# Gamepad.net
KiCad netlist of a schematic drawn in EAGLE
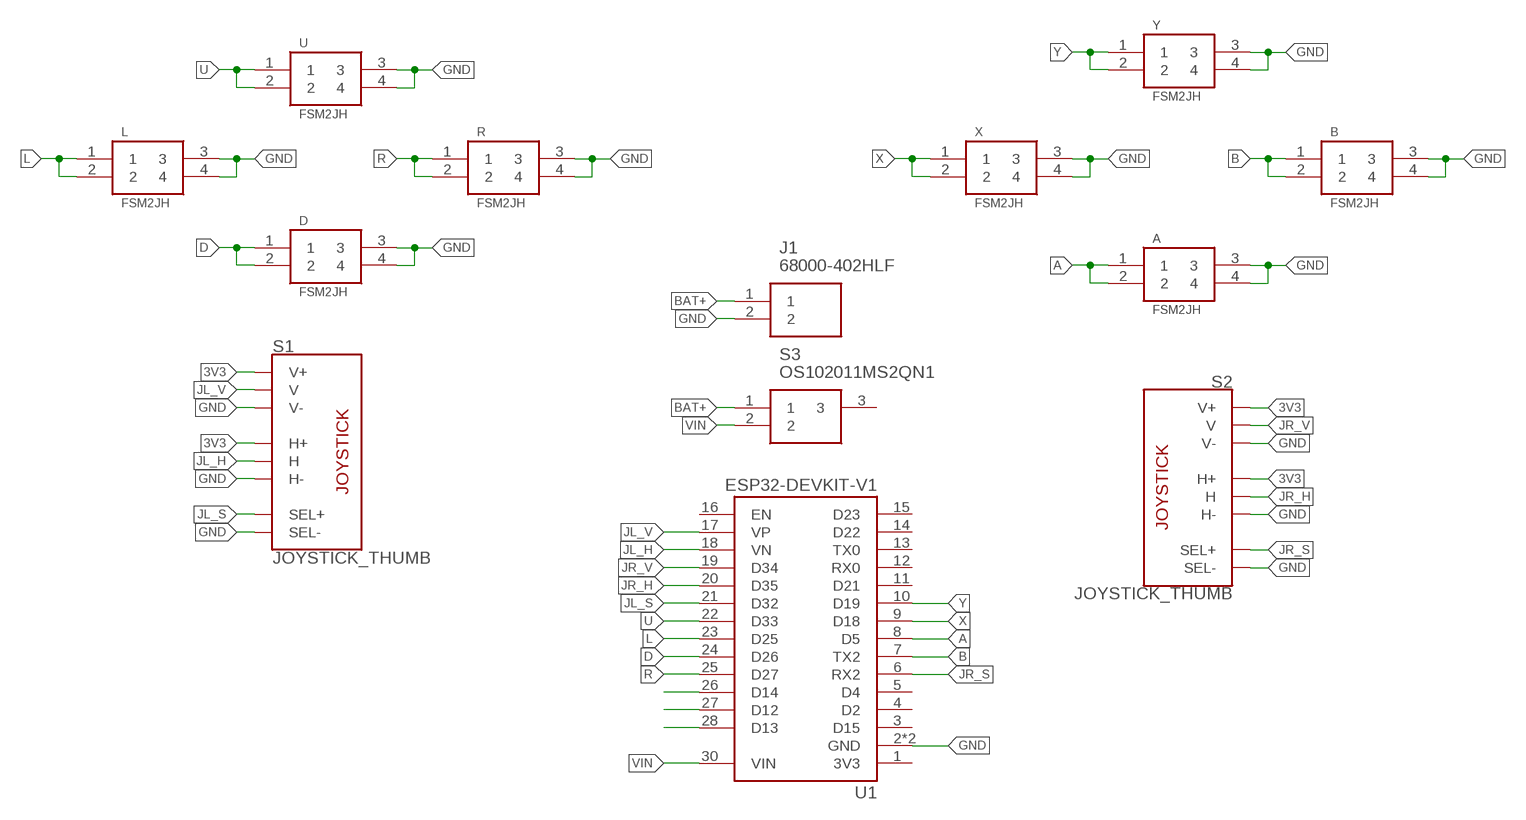
[diagram p0: schematic, sheet 1]

(export (version "E")
  (design (tool "Eeschema 10.0.6"))
  (components
    (comp (ref "A")
      (value "FSM2JH")
      (footprint "eagle-import:FSM2JH")
      (libsource (lib "eagle-import") (part "FSM2JH"))
    )
    (comp (ref "B")
      (value "FSM2JH")
      (footprint "eagle-import:FSM2JH")
      (libsource (lib "eagle-import") (part "FSM2JH"))
    )
    (comp (ref "D")
      (value "FSM2JH")
      (footprint "eagle-import:FSM2JH")
      (libsource (lib "eagle-import") (part "FSM2JH"))
    )
    (comp (ref "J1")
      (value "68000-402HLF")
      (footprint "eagle-import:68000-402HLF")
      (fields (field (name "MOUSER_PART_NUMBER") "649-68000-402HLF"))
      (libsource (lib "eagle-import") (part "68000-402HLF"))
    )
    (comp (ref "L")
      (value "FSM2JH")
      (footprint "eagle-import:FSM2JH")
      (libsource (lib "eagle-import") (part "FSM2JH"))
    )
    (comp (ref "R")
      (value "FSM2JH")
      (footprint "eagle-import:FSM2JH")
      (libsource (lib "eagle-import") (part "FSM2JH"))
    )
    (comp (ref "S1")
      (value "JOYSTICK_THUMB")
      (footprint "eagle-import:JOYSTICK")
      (libsource (lib "eagle-import") (part "JOYSTICK_THUMB"))
    )
    (comp (ref "S2")
      (value "JOYSTICK_THUMB")
      (footprint "eagle-import:JOYSTICK")
      (libsource (lib "eagle-import") (part "JOYSTICK_THUMB"))
    )
    (comp (ref "S3")
      (value "OS102011MS2QN1")
      (footprint "eagle-import:OS102011MA1QN1")
      (fields (field (name "RS_PART_NUMBER") "7874864"))
      (libsource (lib "eagle-import") (part "OS102011MS2QN1"))
    )
    (comp (ref "U")
      (value "FSM2JH")
      (footprint "eagle-import:FSM2JH")
      (libsource (lib "eagle-import") (part "FSM2JH"))
    )
    (comp (ref "U1")
      (value "ESP32-DEVKIT-V1")
      (footprint "eagle-import:MODULE_ESP32_DEVKIT_V1")
      (fields (field (name "MF") "Do it"))
      (libsource (lib "eagle-import") (part "ESP32-DEVKIT-V1"))
    )
    (comp (ref "X")
      (value "FSM2JH")
      (footprint "eagle-import:FSM2JH")
      (libsource (lib "eagle-import") (part "FSM2JH"))
    )
    (comp (ref "Y")
      (value "FSM2JH")
      (footprint "eagle-import:FSM2JH")
      (libsource (lib "eagle-import") (part "FSM2JH"))
    )
  )
  (nets
    (net (code "1") (name "3V3") (class "Default")
      (node (ref "S1") (pin "H1") (pinfunction "H+_H1") (pintype "bidirectional"))
      (node (ref "S1") (pin "V1") (pinfunction "V+_V1") (pintype "bidirectional"))
      (node (ref "S2") (pin "H1") (pinfunction "H+_H1") (pintype "bidirectional"))
      (node (ref "S2") (pin "V1") (pinfunction "V+_V1") (pintype "bidirectional"))
    )
    (net (code "2") (name "A") (class "Default")
      (node (ref "A") (pin "1") (pinfunction "1_1") (pintype "bidirectional"))
      (node (ref "A") (pin "2") (pinfunction "2_2") (pintype "bidirectional"))
      (node (ref "U1") (pin "8") (pinfunction "D5_8") (pintype "bidirectional"))
    )
    (net (code "3") (name "B") (class "Default")
      (node (ref "B") (pin "1") (pinfunction "1_1") (pintype "bidirectional"))
      (node (ref "B") (pin "2") (pinfunction "2_2") (pintype "bidirectional"))
      (node (ref "U1") (pin "7") (pinfunction "TX2_7") (pintype "output"))
    )
    (net (code "4") (name "BAT+") (class "Default")
      (node (ref "J1") (pin "1") (pinfunction "1_1") (pintype "bidirectional"))
      (node (ref "S3") (pin "1") (pinfunction "1_1") (pintype "bidirectional"))
    )
    (net (code "5") (name "D") (class "Default")
      (node (ref "D") (pin "1") (pinfunction "1_1") (pintype "bidirectional"))
      (node (ref "D") (pin "2") (pinfunction "2_2") (pintype "bidirectional"))
      (node (ref "U1") (pin "24") (pinfunction "D26_24") (pintype "bidirectional"))
    )
    (net (code "6") (name "GND") (class "Default")
      (node (ref "A") (pin "3") (pinfunction "3_3") (pintype "bidirectional"))
      (node (ref "A") (pin "4") (pinfunction "4_4") (pintype "bidirectional"))
      (node (ref "B") (pin "3") (pinfunction "3_3") (pintype "bidirectional"))
      (node (ref "B") (pin "4") (pinfunction "4_4") (pintype "bidirectional"))
      (node (ref "D") (pin "3") (pinfunction "3_3") (pintype "bidirectional"))
      (node (ref "D") (pin "4") (pinfunction "4_4") (pintype "bidirectional"))
      (node (ref "J1") (pin "2") (pinfunction "2_2") (pintype "bidirectional"))
      (node (ref "L") (pin "3") (pinfunction "3_3") (pintype "bidirectional"))
      (node (ref "L") (pin "4") (pinfunction "4_4") (pintype "bidirectional"))
      (node (ref "R") (pin "3") (pinfunction "3_3") (pintype "bidirectional"))
      (node (ref "R") (pin "4") (pinfunction "4_4") (pintype "bidirectional"))
      (node (ref "S1") (pin "B2A") (pinfunction "SEL-_B2A") (pintype "bidirectional"))
      (node (ref "S1") (pin "H3") (pinfunction "H-_H3") (pintype "bidirectional"))
      (node (ref "S1") (pin "V3") (pinfunction "V-_V3") (pintype "bidirectional"))
      (node (ref "S2") (pin "B2A") (pinfunction "SEL-_B2A") (pintype "bidirectional"))
      (node (ref "S2") (pin "H3") (pinfunction "H-_H3") (pintype "bidirectional"))
      (node (ref "S2") (pin "V3") (pinfunction "V-_V3") (pintype "bidirectional"))
      (node (ref "U") (pin "3") (pinfunction "3_3") (pintype "bidirectional"))
      (node (ref "U") (pin "4") (pinfunction "4_4") (pintype "bidirectional"))
      (node (ref "U1") (pin "2") (pinfunction "GND_2") (pintype "power_in"))
      (node (ref "U1") (pin "29") (pinfunction "GND_29") (pintype "power_in"))
      (node (ref "X") (pin "3") (pinfunction "3_3") (pintype "bidirectional"))
      (node (ref "X") (pin "4") (pinfunction "4_4") (pintype "bidirectional"))
      (node (ref "Y") (pin "3") (pinfunction "3_3") (pintype "bidirectional"))
      (node (ref "Y") (pin "4") (pinfunction "4_4") (pintype "bidirectional"))
    )
    (net (code "7") (name "JL_H") (class "Default")
      (node (ref "S1") (pin "H2") (pinfunction "H_H2") (pintype "bidirectional"))
      (node (ref "U1") (pin "18") (pinfunction "VN_18") (pintype "bidirectional"))
    )
    (net (code "8") (name "JL_S") (class "Default")
      (node (ref "S1") (pin "B1A") (pinfunction "SEL+_B1A") (pintype "bidirectional"))
      (node (ref "U1") (pin "21") (pinfunction "D32_21") (pintype "bidirectional"))
    )
    (net (code "9") (name "JL_V") (class "Default")
      (node (ref "S1") (pin "V2") (pinfunction "V_V2") (pintype "bidirectional"))
      (node (ref "U1") (pin "17") (pinfunction "VP_17") (pintype "bidirectional"))
    )
    (net (code "10") (name "JR_H") (class "Default")
      (node (ref "S2") (pin "H2") (pinfunction "H_H2") (pintype "bidirectional"))
      (node (ref "U1") (pin "20") (pinfunction "D35_20") (pintype "bidirectional"))
    )
    (net (code "11") (name "JR_S") (class "Default")
      (node (ref "S2") (pin "B1A") (pinfunction "SEL+_B1A") (pintype "bidirectional"))
      (node (ref "U1") (pin "6") (pinfunction "RX2_6") (pintype "input"))
    )
    (net (code "12") (name "JR_V") (class "Default")
      (node (ref "S2") (pin "V2") (pinfunction "V_V2") (pintype "bidirectional"))
      (node (ref "U1") (pin "19") (pinfunction "D34_19") (pintype "bidirectional"))
    )
    (net (code "13") (name "L") (class "Default")
      (node (ref "L") (pin "1") (pinfunction "1_1") (pintype "bidirectional"))
      (node (ref "L") (pin "2") (pinfunction "2_2") (pintype "bidirectional"))
      (node (ref "U1") (pin "23") (pinfunction "D25_23") (pintype "bidirectional"))
    )
    (net (code "14") (name "R") (class "Default")
      (node (ref "R") (pin "1") (pinfunction "1_1") (pintype "bidirectional"))
      (node (ref "R") (pin "2") (pinfunction "2_2") (pintype "bidirectional"))
      (node (ref "U1") (pin "25") (pinfunction "D27_25") (pintype "bidirectional"))
    )
    (net (code "15") (name "U") (class "Default")
      (node (ref "U") (pin "1") (pinfunction "1_1") (pintype "bidirectional"))
      (node (ref "U") (pin "2") (pinfunction "2_2") (pintype "bidirectional"))
      (node (ref "U1") (pin "22") (pinfunction "D33_22") (pintype "bidirectional"))
    )
    (net (code "16") (name "VIN") (class "Default")
      (node (ref "S3") (pin "2") (pinfunction "2_2") (pintype "bidirectional"))
      (node (ref "U1") (pin "30") (pinfunction "VIN_30") (pintype "input"))
    )
    (net (code "17") (name "X") (class "Default")
      (node (ref "U1") (pin "9") (pinfunction "D18_9") (pintype "bidirectional"))
      (node (ref "X") (pin "1") (pinfunction "1_1") (pintype "bidirectional"))
      (node (ref "X") (pin "2") (pinfunction "2_2") (pintype "bidirectional"))
    )
    (net (code "18") (name "Y") (class "Default")
      (node (ref "U1") (pin "10") (pinfunction "D19_10") (pintype "bidirectional"))
      (node (ref "Y") (pin "1") (pinfunction "1_1") (pintype "bidirectional"))
      (node (ref "Y") (pin "2") (pinfunction "2_2") (pintype "bidirectional"))
    )
    (net (code "19") (name "unconnected-(S3-Pad3)") (class "Default")
      (node (ref "S3") (pin "3") (pinfunction "3_3") (pintype "bidirectional"))
    )
    (net (code "20") (name "unconnected-(U1-3V3-Pad1)") (class "Default")
      (node (ref "U1") (pin "1") (pinfunction "3V3_1") (pintype "output"))
    )
    (net (code "21") (name "unconnected-(U1-D2-Pad4)") (class "Default")
      (node (ref "U1") (pin "4") (pinfunction "D2_4") (pintype "bidirectional"))
    )
    (net (code "22") (name "unconnected-(U1-D4-Pad5)") (class "Default")
      (node (ref "U1") (pin "5") (pinfunction "D4_5") (pintype "bidirectional"))
    )
    (net (code "23") (name "unconnected-(U1-D12-Pad27)") (class "Default")
      (node (ref "U1") (pin "27") (pinfunction "D12_27") (pintype "bidirectional"))
    )
    (net (code "24") (name "unconnected-(U1-D13-Pad28)") (class "Default")
      (node (ref "U1") (pin "28") (pinfunction "D13_28") (pintype "bidirectional"))
    )
    (net (code "25") (name "unconnected-(U1-D14-Pad26)") (class "Default")
      (node (ref "U1") (pin "26") (pinfunction "D14_26") (pintype "bidirectional"))
    )
    (net (code "26") (name "unconnected-(U1-D15-Pad3)") (class "Default")
      (node (ref "U1") (pin "3") (pinfunction "D15_3") (pintype "bidirectional"))
    )
    (net (code "27") (name "unconnected-(U1-D21-Pad11)") (class "Default")
      (node (ref "U1") (pin "11") (pinfunction "D21_11") (pintype "bidirectional"))
    )
    (net (code "28") (name "unconnected-(U1-D22-Pad14)") (class "Default")
      (node (ref "U1") (pin "14") (pinfunction "D22_14") (pintype "bidirectional"))
    )
    (net (code "29") (name "unconnected-(U1-D23-Pad15)") (class "Default")
      (node (ref "U1") (pin "15") (pinfunction "D23_15") (pintype "bidirectional"))
    )
    (net (code "30") (name "unconnected-(U1-EN-Pad16)") (class "Default")
      (node (ref "U1") (pin "16") (pinfunction "EN_16") (pintype "input"))
    )
    (net (code "31") (name "unconnected-(U1-RX0-Pad12)") (class "Default")
      (node (ref "U1") (pin "12") (pinfunction "RX0_12") (pintype "input"))
    )
    (net (code "32") (name "unconnected-(U1-TX0-Pad13)") (class "Default")
      (node (ref "U1") (pin "13") (pinfunction "TX0_13") (pintype "output"))
    )
  )
)
